# untitled.net
KiCad netlist of a schematic drawn in EAGLE
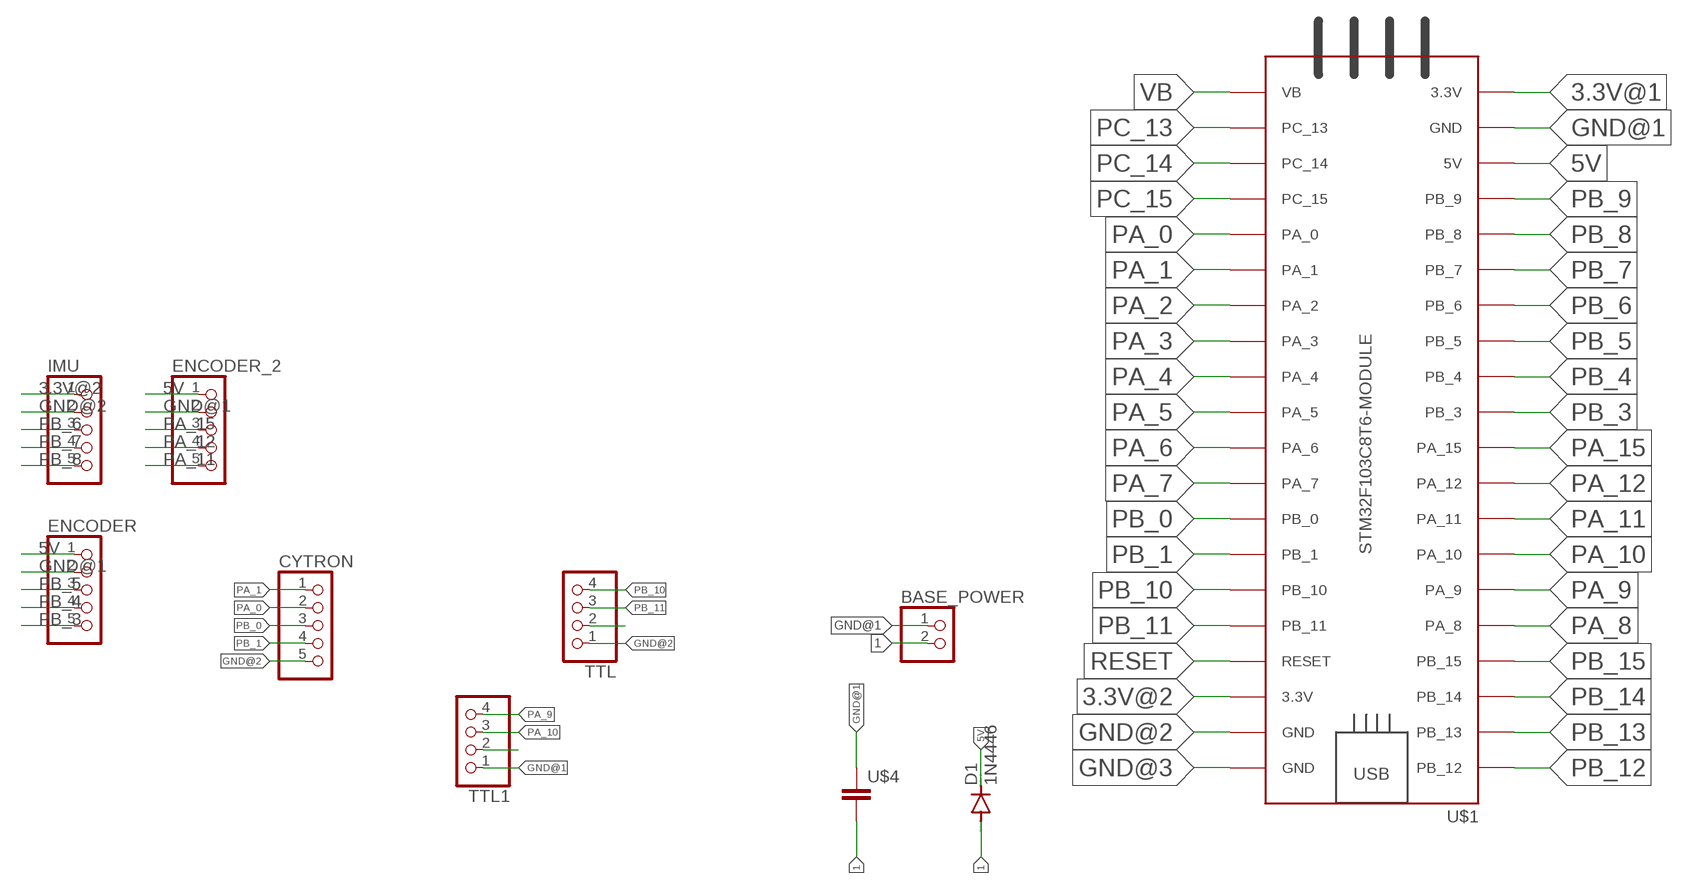
[diagram p0: schematic, sheet 1]

(export (version "E")
  (design (tool "Eeschema 10.0.6"))
  (components
    (comp (ref "BASE_POWER")
      (value "PINHD-2_DATA")
      (footprint "eagle-import:1X02_DATA")
      (libsource (lib "eagle-import") (part "PINHD-2_DATA"))
    )
    (comp (ref "CYTRON")
      (value "PINHD-5_DATA")
      (footprint "eagle-import:1X05_DATA")
      (libsource (lib "eagle-import") (part "PINHD-5_DATA"))
    )
    (comp (ref "D1")
      (value "1N4446")
      (footprint "eagle-import:DO35-10")
      (libsource (lib "eagle-import") (part "1N4446"))
    )
    (comp (ref "ENCODER")
      (value "PINHD-5_DATA")
      (footprint "eagle-import:1X05_DATA")
      (libsource (lib "eagle-import") (part "PINHD-5_DATA"))
    )
    (comp (ref "ENCODER_2")
      (value "PINHD-5_DATA")
      (footprint "eagle-import:1X05_DATA")
      (libsource (lib "eagle-import") (part "PINHD-5_DATA"))
    )
    (comp (ref "IMU")
      (value "PINHD-5_DATA")
      (footprint "eagle-import:1X05_DATA")
      (libsource (lib "eagle-import") (part "PINHD-5_DATA"))
    )
    (comp (ref "TTL")
      (value "PINHD-4_DATA")
      (footprint "eagle-import:1X04_DATA")
      (libsource (lib "eagle-import") (part "PINHD-4_DATA"))
    )
    (comp (ref "TTL1")
      (value "PINHD-4_DATA")
      (footprint "eagle-import:1X04_DATA")
      (libsource (lib "eagle-import") (part "PINHD-4_DATA"))
    )
    (comp (ref "U$1")
      (value "STM32F103C8T6-MODULE")
      (footprint "eagle-import:STM32F103C8T6-MODULE")
      (libsource (lib "eagle-import") (part "STM32F103C8T6-MODULE"))
    )
    (comp (ref "U$4")
      (value "CAPACITOR")
      (footprint "eagle-import:C025-025X050")
      (libsource (lib "eagle-import") (part "CAPACITOR"))
    )
  )
  (nets
    (net (code "1") (name "1") (class "Default")
      (node (ref "BASE_POWER") (pin "2") (pinfunction "2_2") (pintype "passive"))
      (node (ref "D1") (pin "A") (pinfunction "A_A") (pintype "passive"))
      (node (ref "U$4") (pin "2") (pinfunction "2_2") (pintype "passive"))
    )
    (net (code "2") (name "3.3V@1") (class "Default")
      (node (ref "U$1") (pin "3.3V_1") (pinfunction "3.3V_3.3V_1") (pintype "bidirectional"))
    )
    (net (code "3") (name "3.3V@2") (class "Default")
      (node (ref "IMU") (pin "1") (pinfunction "1_1") (pintype "passive"))
      (node (ref "U$1") (pin "3.3V_2") (pinfunction "3.3V_3.3V_2") (pintype "bidirectional"))
    )
    (net (code "4") (name "5V") (class "Default")
      (node (ref "D1") (pin "C") (pinfunction "C_C") (pintype "passive"))
      (node (ref "ENCODER") (pin "1") (pinfunction "1_1") (pintype "passive"))
      (node (ref "ENCODER_2") (pin "1") (pinfunction "1_1") (pintype "passive"))
      (node (ref "TTL") (pin "2") (pinfunction "2_2") (pintype "passive"))
      (node (ref "TTL1") (pin "2") (pinfunction "2_2") (pintype "passive"))
      (node (ref "U$1") (pin "5V") (pinfunction "5V_5V") (pintype "bidirectional"))
    )
    (net (code "5") (name "GND@1") (class "Default")
      (node (ref "BASE_POWER") (pin "1") (pinfunction "1_1") (pintype "passive"))
      (node (ref "ENCODER") (pin "2") (pinfunction "2_2") (pintype "passive"))
      (node (ref "ENCODER_2") (pin "2") (pinfunction "2_2") (pintype "passive"))
      (node (ref "TTL1") (pin "1") (pinfunction "1_1") (pintype "passive"))
      (node (ref "U$1") (pin "GND_1") (pinfunction "GND_GND_1") (pintype "bidirectional"))
      (node (ref "U$4") (pin "1") (pinfunction "1_1") (pintype "passive"))
    )
    (net (code "6") (name "GND@2") (class "Default")
      (node (ref "CYTRON") (pin "5") (pinfunction "5_5") (pintype "passive"))
      (node (ref "IMU") (pin "2") (pinfunction "2_2") (pintype "passive"))
      (node (ref "TTL") (pin "1") (pinfunction "1_1") (pintype "passive"))
      (node (ref "U$1") (pin "GND_2") (pinfunction "GND_GND_2") (pintype "bidirectional"))
    )
    (net (code "7") (name "GND@3") (class "Default")
      (node (ref "U$1") (pin "GND_3") (pinfunction "GND_GND_3") (pintype "power_in"))
    )
    (net (code "8") (name "PA_0") (class "Default")
      (node (ref "CYTRON") (pin "2") (pinfunction "2_2") (pintype "passive"))
      (node (ref "U$1") (pin "PA_0") (pinfunction "PA_0_PA_0") (pintype "bidirectional"))
    )
    (net (code "9") (name "PA_1") (class "Default")
      (node (ref "CYTRON") (pin "1") (pinfunction "1_1") (pintype "passive"))
      (node (ref "U$1") (pin "PA_1") (pinfunction "PA_1_PA_1") (pintype "bidirectional"))
    )
    (net (code "10") (name "PA_2") (class "Default")
      (node (ref "U$1") (pin "PA_2") (pinfunction "PA_2_PA_2") (pintype "bidirectional"))
    )
    (net (code "11") (name "PA_3") (class "Default")
      (node (ref "U$1") (pin "PA_3") (pinfunction "PA_3_PA_3") (pintype "bidirectional"))
    )
    (net (code "12") (name "PA_4") (class "Default")
      (node (ref "U$1") (pin "PA_4") (pinfunction "PA_4_PA_4") (pintype "bidirectional"))
    )
    (net (code "13") (name "PA_5") (class "Default")
      (node (ref "U$1") (pin "PA_5") (pinfunction "PA_5_PA_5") (pintype "bidirectional"))
    )
    (net (code "14") (name "PA_6") (class "Default")
      (node (ref "U$1") (pin "PA_6") (pinfunction "PA_6_PA_6") (pintype "bidirectional"))
    )
    (net (code "15") (name "PA_7") (class "Default")
      (node (ref "U$1") (pin "PA_7") (pinfunction "PA_7_PA_7") (pintype "bidirectional"))
    )
    (net (code "16") (name "PA_8") (class "Default")
      (node (ref "U$1") (pin "PA_8") (pinfunction "PA_8_PA_8") (pintype "bidirectional"))
    )
    (net (code "17") (name "PA_9") (class "Default")
      (node (ref "TTL1") (pin "4") (pinfunction "4_4") (pintype "passive"))
      (node (ref "U$1") (pin "PA_9") (pinfunction "PA_9_PA_9") (pintype "bidirectional"))
    )
    (net (code "18") (name "PA_10") (class "Default")
      (node (ref "TTL1") (pin "3") (pinfunction "3_3") (pintype "passive"))
      (node (ref "U$1") (pin "PA_10") (pinfunction "PA_10_PA_10") (pintype "bidirectional"))
    )
    (net (code "19") (name "PA_11") (class "Default")
      (node (ref "ENCODER_2") (pin "5") (pinfunction "5_5") (pintype "passive"))
      (node (ref "U$1") (pin "PA_11") (pinfunction "PA_11_PA_11") (pintype "bidirectional"))
    )
    (net (code "20") (name "PA_12") (class "Default")
      (node (ref "ENCODER_2") (pin "4") (pinfunction "4_4") (pintype "passive"))
      (node (ref "U$1") (pin "PA_12") (pinfunction "PA_12_PA_12") (pintype "bidirectional"))
    )
    (net (code "21") (name "PA_15") (class "Default")
      (node (ref "ENCODER_2") (pin "3") (pinfunction "3_3") (pintype "passive"))
      (node (ref "U$1") (pin "PA_15") (pinfunction "PA_15_PA_15") (pintype "bidirectional"))
    )
    (net (code "22") (name "PB_0") (class "Default")
      (node (ref "CYTRON") (pin "3") (pinfunction "3_3") (pintype "passive"))
      (node (ref "U$1") (pin "PB_0") (pinfunction "PB_0_PB_0") (pintype "bidirectional"))
    )
    (net (code "23") (name "PB_1") (class "Default")
      (node (ref "CYTRON") (pin "4") (pinfunction "4_4") (pintype "passive"))
      (node (ref "U$1") (pin "PB_1") (pinfunction "PB_1_PB_1") (pintype "bidirectional"))
    )
    (net (code "24") (name "PB_3") (class "Default")
      (node (ref "ENCODER") (pin "5") (pinfunction "5_5") (pintype "passive"))
      (node (ref "U$1") (pin "PB_3") (pinfunction "PB_3_PB_3") (pintype "bidirectional"))
    )
    (net (code "25") (name "PB_4") (class "Default")
      (node (ref "ENCODER") (pin "4") (pinfunction "4_4") (pintype "passive"))
      (node (ref "U$1") (pin "PB_4") (pinfunction "PB_4_PB_4") (pintype "bidirectional"))
    )
    (net (code "26") (name "PB_5") (class "Default")
      (node (ref "ENCODER") (pin "3") (pinfunction "3_3") (pintype "passive"))
      (node (ref "U$1") (pin "PB_5") (pinfunction "PB_5_PB_5") (pintype "bidirectional"))
    )
    (net (code "27") (name "PB_6") (class "Default")
      (node (ref "IMU") (pin "3") (pinfunction "3_3") (pintype "passive"))
      (node (ref "U$1") (pin "PB_6") (pinfunction "PB_6_PB_6") (pintype "bidirectional"))
    )
    (net (code "28") (name "PB_7") (class "Default")
      (node (ref "IMU") (pin "4") (pinfunction "4_4") (pintype "passive"))
      (node (ref "U$1") (pin "PB_7") (pinfunction "PB_7_PB_7") (pintype "bidirectional"))
    )
    (net (code "29") (name "PB_8") (class "Default")
      (node (ref "IMU") (pin "5") (pinfunction "5_5") (pintype "passive"))
      (node (ref "U$1") (pin "PB_8") (pinfunction "PB_8_PB_8") (pintype "bidirectional"))
    )
    (net (code "30") (name "PB_9") (class "Default")
      (node (ref "U$1") (pin "PB_9") (pinfunction "PB_9_PB_9") (pintype "bidirectional"))
    )
    (net (code "31") (name "PB_10") (class "Default")
      (node (ref "TTL") (pin "4") (pinfunction "4_4") (pintype "passive"))
      (node (ref "U$1") (pin "PB_10") (pinfunction "PB_10_PB_10") (pintype "bidirectional"))
    )
    (net (code "32") (name "PB_11") (class "Default")
      (node (ref "TTL") (pin "3") (pinfunction "3_3") (pintype "passive"))
      (node (ref "U$1") (pin "PB_11") (pinfunction "PB_11_PB_11") (pintype "bidirectional"))
    )
    (net (code "33") (name "PB_12") (class "Default")
      (node (ref "U$1") (pin "PB_12") (pinfunction "PB_12_PB_12") (pintype "bidirectional"))
    )
    (net (code "34") (name "PB_13") (class "Default")
      (node (ref "U$1") (pin "PB_13") (pinfunction "PB_13_PB_13") (pintype "bidirectional"))
    )
    (net (code "35") (name "PB_14") (class "Default")
      (node (ref "U$1") (pin "PB_14") (pinfunction "PB_14_PB_14") (pintype "bidirectional"))
    )
    (net (code "36") (name "PB_15") (class "Default")
      (node (ref "U$1") (pin "PB_15") (pinfunction "PB_15_PB_15") (pintype "bidirectional"))
    )
    (net (code "37") (name "PC_13") (class "Default")
      (node (ref "U$1") (pin "PC_13") (pinfunction "PC_13_PC_13") (pintype "bidirectional"))
    )
    (net (code "38") (name "PC_14") (class "Default")
      (node (ref "U$1") (pin "PC_14") (pinfunction "PC_14_PC_14") (pintype "bidirectional"))
    )
    (net (code "39") (name "PC_15") (class "Default")
      (node (ref "U$1") (pin "PC_15") (pinfunction "PC_15_PC_15") (pintype "bidirectional"))
    )
    (net (code "40") (name "RESET") (class "Default")
      (node (ref "U$1") (pin "RESET") (pinfunction "RESET_RESET") (pintype "bidirectional"))
    )
    (net (code "41") (name "VB") (class "Default")
      (node (ref "U$1") (pin "VB") (pinfunction "VB_VB") (pintype "bidirectional"))
    )
  )
)
